# Electrotactile.net
KiCad netlist of a schematic drawn in Altium Designer
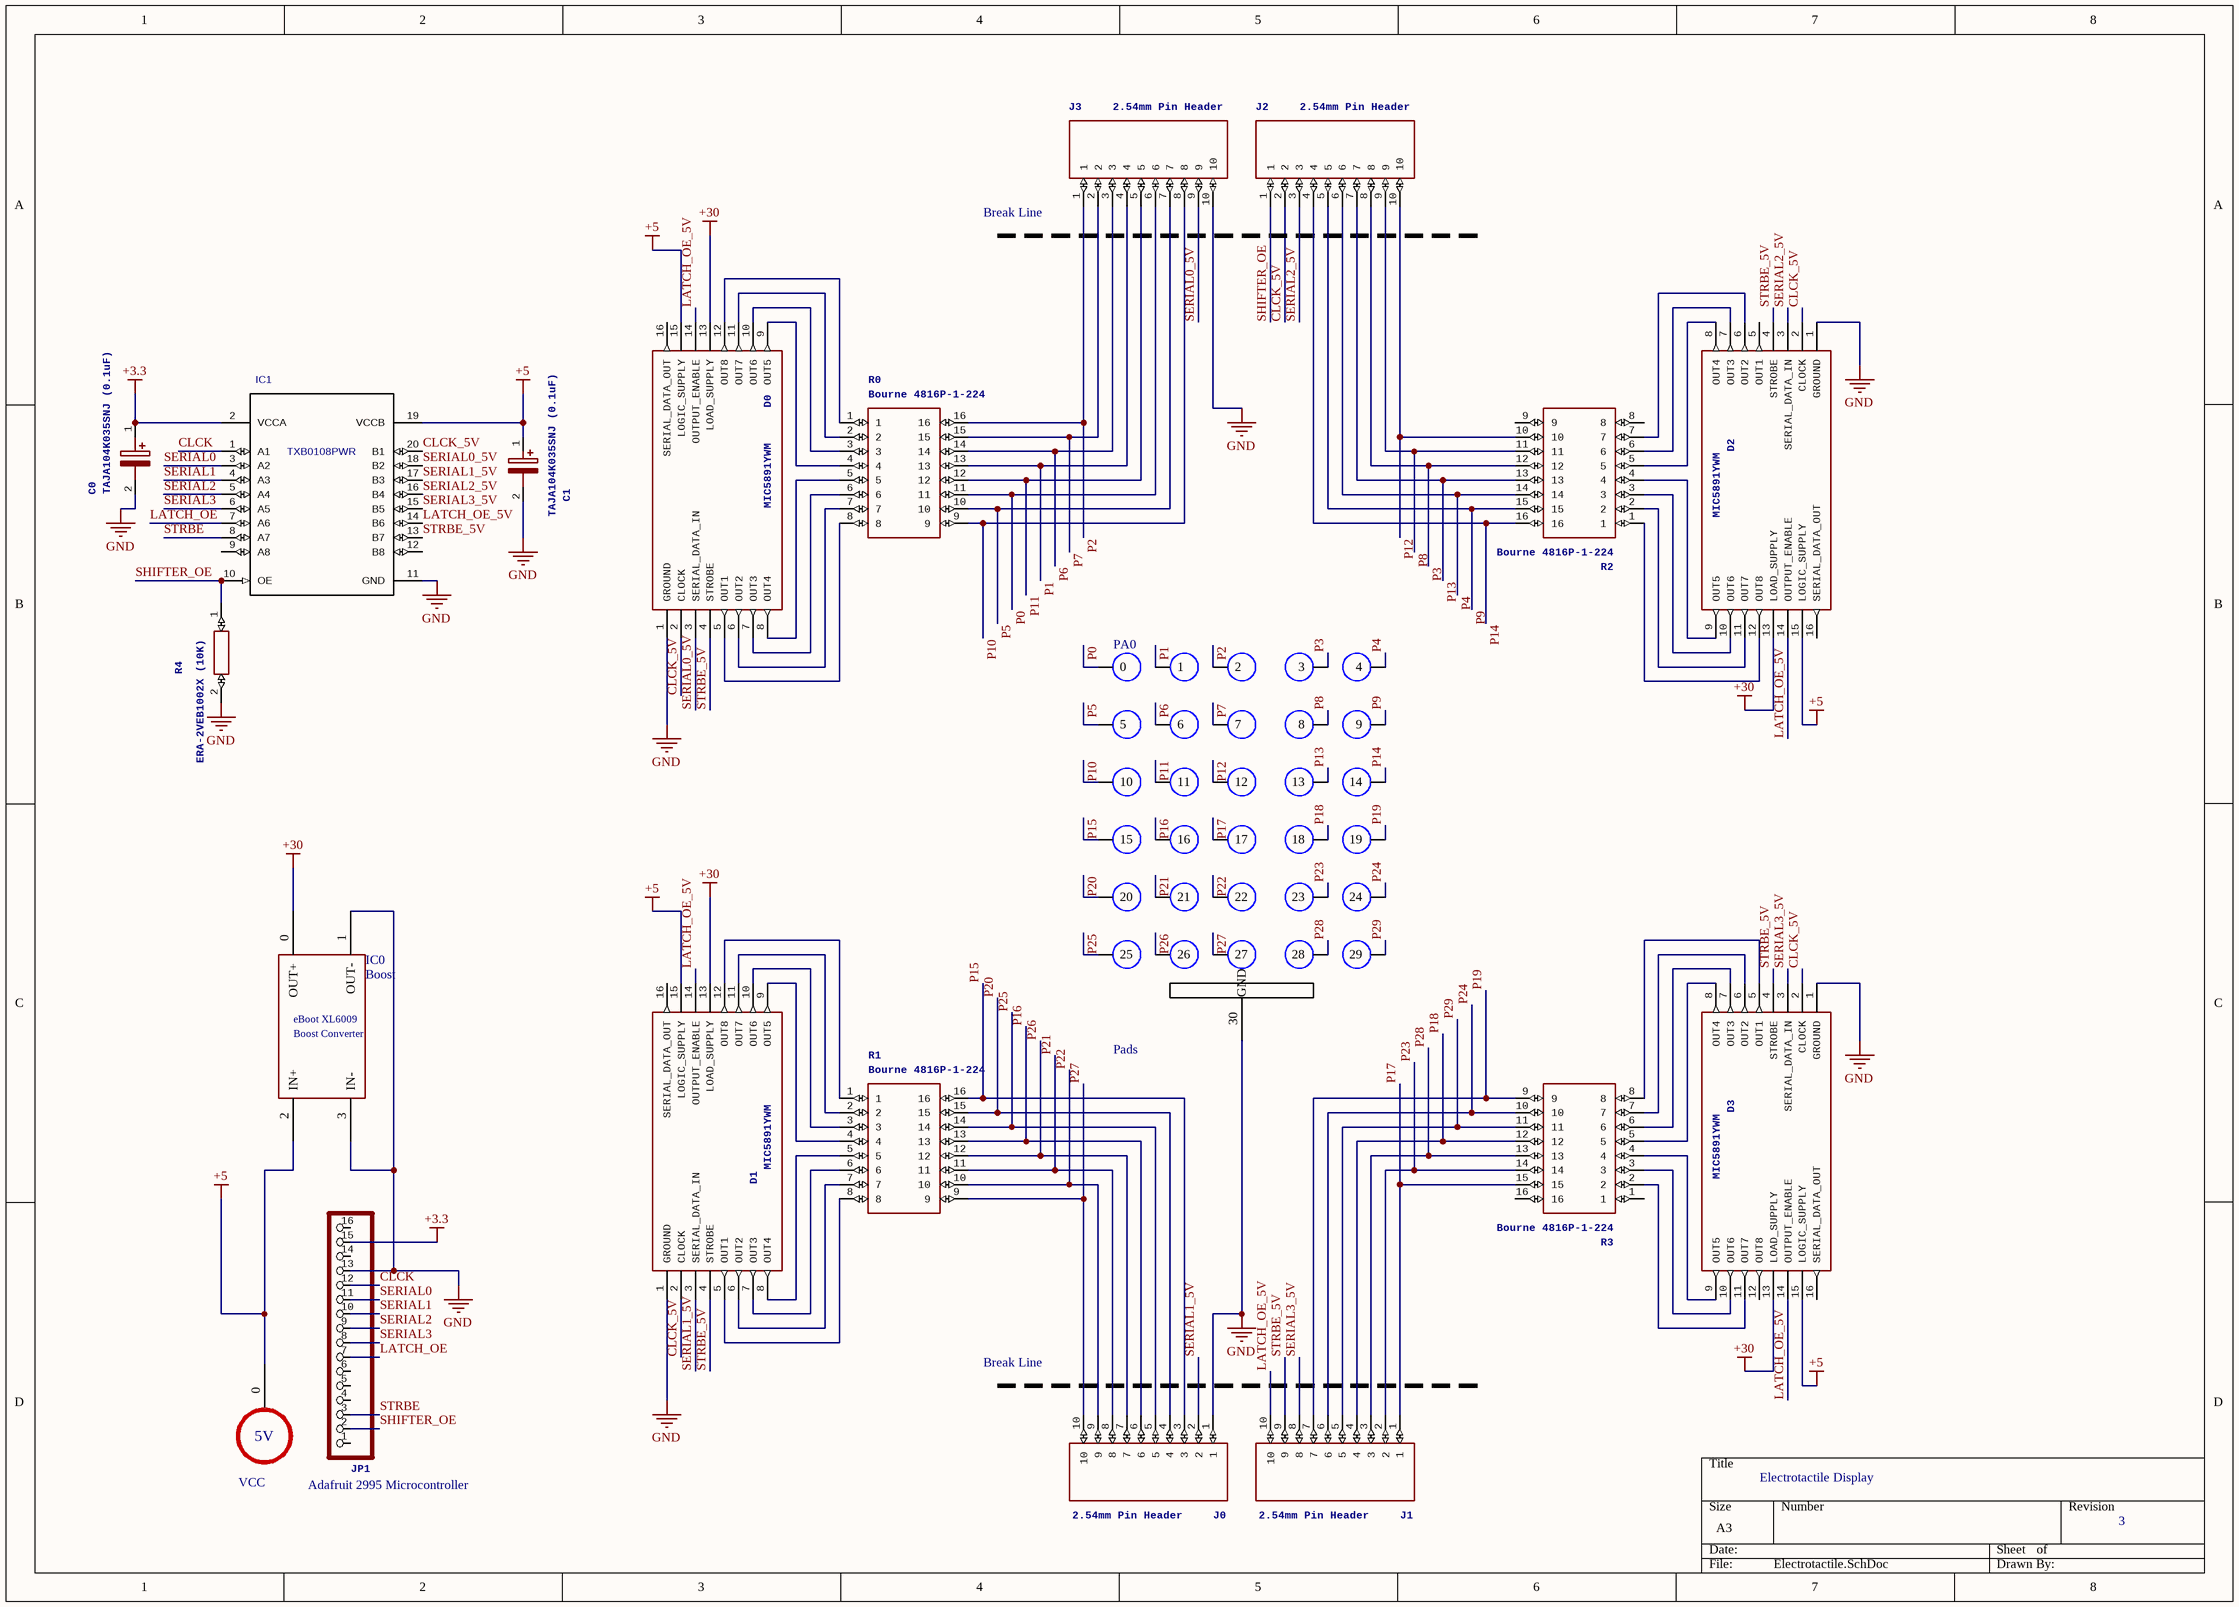
[diagram p0: Electrotactile.SchDoc]

(export (version "E")
  (design (tool "Eeschema 10.0.6"))
  (components
    (comp (ref "C0")
      (value "TAJA104K035SNJ (0.1uF)")
      (footprint "CAPPM3216X180N")
      (fields
        (field (name "MOUSER_PART_NUMBER") "581-TAJA104K035SNJ")
        (field (name "MANUFACTURER_PART_NUMBER") "TAJA104K035SNJ")
      )
      (libsource (lib "") (part "TAJA104K035SNJ_1"))
    )
    (comp (ref "C1")
      (value "TAJA104K035SNJ (0.1uF)")
      (footprint "CAPPM3216X180N")
      (fields
        (field (name "MOUSER_PART_NUMBER") "581-TAJA104K035SNJ")
        (field (name "MANUFACTURER_PART_NUMBER") "TAJA104K035SNJ")
      )
      (libsource (lib "TAJA104K035SNJ") (part "TAJA104K035SNJ"))
    )
    (comp (ref "D0")
      (value "MIC5891YWM")
      (footprint "SOIC127P1031X264-16N")
      (fields (field (name "MOUSER_PART_NUMBER") "998-MIC5891YWM"))
      (libsource (lib "MIC5891YWM") (part "MIC5891YWM"))
    )
    (comp (ref "D1")
      (value "MIC5891YWM")
      (footprint "SOIC127P1031X264-16N")
      (fields (field (name "MOUSER_PART_NUMBER") "998-MIC5891YWM"))
      (libsource (lib "MIC5891YWM") (part "MIC5891YWM"))
    )
    (comp (ref "D2")
      (value "MIC5891YWM")
      (footprint "SOIC127P1031X264-16N")
      (fields (field (name "MOUSER_PART_NUMBER") "998-MIC5891YWM"))
      (libsource (lib "MIC5891YWM") (part "MIC5891YWM"))
    )
    (comp (ref "D3")
      (value "MIC5891YWM")
      (footprint "SOIC127P1031X264-16N")
      (fields (field (name "MOUSER_PART_NUMBER") "998-MIC5891YWM"))
      (libsource (lib "MIC5891YWM") (part "MIC5891YWM"))
    )
    (comp (ref "IC0") (value "Boost") (footprint "Boost Pads") (libsource (lib "Boost") (part "Boost")))
    (comp (ref "IC1")
      (value "TXB0108PWR")
      (footprint "SOP65P640X120-20N")
      (fields (field (name "MANUFACTURER") "Texas Instruments"))
      (libsource (lib "AltiumV15") (part "TXB0108PWR"))
    )
    (comp (ref "J0")
      (value "2.54mm Pin Header")
      (footprint "HDRV10W64P0X254_1X10_2540X254X")
      (fields
        (field (name "MOUSER_PART_NUMBER") "710-61301011121")
        (field (name "MANUFACTURER_PART_NUMBER") "61301011121")
      )
      (libsource (lib "61301011121") (part "61301011121"))
    )
    (comp (ref "J1")
      (value "2.54mm Pin Header")
      (footprint "HDRV10W64P0X254_1X10_2540X254X")
      (fields
        (field (name "MOUSER_PART_NUMBER") "710-61301011121")
        (field (name "MANUFACTURER_PART_NUMBER") "61301011121")
      )
      (libsource (lib "61301011121") (part "61301011121"))
    )
    (comp (ref "J2")
      (value "2.54mm Pin Header")
      (footprint "HDRV10W64P0X254_1X10_2540X254X")
      (fields
        (field (name "MOUSER_PART_NUMBER") "710-61301011121")
        (field (name "MANUFACTURER_PART_NUMBER") "61301011121")
      )
      (libsource (lib "61301011121") (part "61301011121"))
    )
    (comp (ref "J3")
      (value "2.54mm Pin Header")
      (footprint "HDRV10W64P0X254_1X10_2540X254X")
      (fields
        (field (name "MOUSER_PART_NUMBER") "710-61301011121")
        (field (name "MANUFACTURER_PART_NUMBER") "61301011121")
      )
      (libsource (lib "61301011121") (part "61301011121"))
    )
    (comp (ref "JP1")
      (value "HEADER-1X16ROUND")
      (footprint "header_x16")
      (description "PIN HEADER")
      (libsource (lib "microbuilder") (part "HEADER-1X16ROUND"))
    )
    (comp (ref "PA0") (value "Pads") (footprint "Pads_Grid") (libsource (lib "pads") (part "Pads")))
    (comp (ref "R0")
      (value "Bourne 4816P-1-224")
      (footprint "SOIC127P762X215-16N")
      (fields
        (field (name "MOUSER_PART_NUMBER") "652-4816P-1LF-22K")
        (field (name "MANUFACTURER_PART_NUMBER") "4816P-1-223LF")
      )
      (libsource (lib "4816P-1-223LF") (part "4816P-1-223LF"))
    )
    (comp (ref "R1")
      (value "Bourne 4816P-1-224")
      (footprint "SOIC127P762X215-16N")
      (fields
        (field (name "MOUSER_PART_NUMBER") "652-4816P-1LF-22K")
        (field (name "MANUFACTURER_PART_NUMBER") "4816P-1-223LF")
      )
      (libsource (lib "4816P-1-223LF") (part "4816P-1-223LF"))
    )
    (comp (ref "R2")
      (value "Bourne 4816P-1-224")
      (footprint "SOIC127P762X215-16N")
      (fields
        (field (name "MOUSER_PART_NUMBER") "652-4816P-1LF-22K")
        (field (name "MANUFACTURER_PART_NUMBER") "4816P-1-223LF")
      )
      (libsource (lib "4816P-1-223LF") (part "4816P-1-223LF"))
    )
    (comp (ref "R3")
      (value "Bourne 4816P-1-224")
      (footprint "SOIC127P762X215-16N")
      (fields
        (field (name "MOUSER_PART_NUMBER") "652-4816P-1LF-22K")
        (field (name "MANUFACTURER_PART_NUMBER") "4816P-1-223LF")
      )
      (libsource (lib "4816P-1-223LF") (part "4816P-1-223LF"))
    )
    (comp (ref "R4")
      (value "ERA-2VEB1002X (10K)")
      (footprint "RESC1005X40N")
      (fields
        (field (name "MOUSER_PART_NUMBER") "667-ERA-2VEB1002X")
        (field (name "MANUFACTURER_PART_NUMBER") "ERA-2VEB1002X")
      )
      (libsource (lib "ERA-2VEB1002X") (part "ERA-2VEB1002X"))
    )
    (comp (ref "VCC") (value "5V") (footprint "5v_Port") (libsource (lib "5V_Port") (part "Component_1")))
  )
  (nets
    (net (code "1") (name "+3.3") (class "Default")
      (node (ref "C0") (pin "1") (pinfunction "+_1") (pintype "bidirectional"))
      (node (ref "IC1") (pin "2") (pinfunction "VCCA_2") (pintype "power_in"))
      (node (ref "JP1") (pin "15") (pinfunction "15_15") (pintype "passive"))
    )
    (net (code "2") (name "+5") (class "Default")
      (node (ref "C1") (pin "1") (pinfunction "+_1") (pintype "bidirectional"))
      (node (ref "D0") (pin "15") (pinfunction "LOGIC_SUPPLY_15") (pintype "power_in"))
      (node (ref "D1") (pin "15") (pinfunction "LOGIC_SUPPLY_15") (pintype "power_in"))
      (node (ref "D2") (pin "15") (pinfunction "LOGIC_SUPPLY_15") (pintype "power_in"))
      (node (ref "D3") (pin "15") (pinfunction "LOGIC_SUPPLY_15") (pintype "power_in"))
      (node (ref "IC0") (pin "2") (pinfunction "IN+_2") (pintype "passive"))
      (node (ref "IC1") (pin "19") (pinfunction "VCCB_19") (pintype "power_in"))
      (node (ref "VCC") (pin "0") (pinfunction "31_0") (pintype "passive"))
    )
    (net (code "3") (name "+30") (class "Default")
      (node (ref "D0") (pin "13") (pinfunction "LOAD_SUPPLY_13") (pintype "power_in"))
      (node (ref "D1") (pin "13") (pinfunction "LOAD_SUPPLY_13") (pintype "power_in"))
      (node (ref "D2") (pin "13") (pinfunction "LOAD_SUPPLY_13") (pintype "power_in"))
      (node (ref "D3") (pin "13") (pinfunction "LOAD_SUPPLY_13") (pintype "power_in"))
      (node (ref "IC0") (pin "0") (pinfunction "OUT+_0") (pintype "passive"))
    )
    (net (code "4") (name "/CLCK") (class "Default")
      (node (ref "IC1") (pin "1") (pinfunction "A1_1") (pintype "bidirectional"))
      (node (ref "JP1") (pin "12") (pinfunction "12_12") (pintype "passive"))
    )
    (net (code "5") (name "/CLCK_5V") (class "Default")
      (node (ref "D0") (pin "2") (pinfunction "CLOCK_2") (pintype "passive"))
      (node (ref "D1") (pin "2") (pinfunction "CLOCK_2") (pintype "passive"))
      (node (ref "D2") (pin "2") (pinfunction "CLOCK_2") (pintype "passive"))
      (node (ref "D3") (pin "2") (pinfunction "CLOCK_2") (pintype "passive"))
      (node (ref "IC1") (pin "20") (pinfunction "B1_20") (pintype "bidirectional"))
      (node (ref "J2") (pin "2") (pinfunction "2_2") (pintype "bidirectional"))
    )
    (net (code "6") (name "/LATCH_OE") (class "Default")
      (node (ref "IC1") (pin "7") (pinfunction "A6_7") (pintype "bidirectional"))
      (node (ref "JP1") (pin "7") (pinfunction "7_7") (pintype "passive"))
    )
    (net (code "7") (name "/LATCH_OE_5V") (class "Default")
      (node (ref "D0") (pin "14") (pinfunction "OUTPUT_ENABLE_14") (pintype "passive"))
      (node (ref "D1") (pin "14") (pinfunction "OUTPUT_ENABLE_14") (pintype "passive"))
      (node (ref "D2") (pin "14") (pinfunction "OUTPUT_ENABLE_14") (pintype "passive"))
      (node (ref "D3") (pin "14") (pinfunction "OUTPUT_ENABLE_14") (pintype "passive"))
      (node (ref "IC1") (pin "14") (pinfunction "B6_14") (pintype "bidirectional"))
      (node (ref "J1") (pin "10") (pinfunction "10_10") (pintype "bidirectional"))
    )
    (net (code "8") (name "/P0") (class "Default")
      (node (ref "J3") (pin "6") (pinfunction "6_6") (pintype "bidirectional"))
      (node (ref "PA0") (pin "0") (pinfunction "0_0") (pintype "passive"))
      (node (ref "R0") (pin "11") (pinfunction "11_11") (pintype "bidirectional"))
    )
    (net (code "9") (name "/P1") (class "Default")
      (node (ref "J3") (pin "4") (pinfunction "4_4") (pintype "bidirectional"))
      (node (ref "PA0") (pin "1") (pinfunction "1_1") (pintype "passive"))
      (node (ref "R0") (pin "13") (pinfunction "13_13") (pintype "bidirectional"))
    )
    (net (code "10") (name "/P2") (class "Default")
      (node (ref "J3") (pin "1") (pinfunction "1_1") (pintype "bidirectional"))
      (node (ref "PA0") (pin "2") (pinfunction "2_2") (pintype "passive"))
      (node (ref "R0") (pin "16") (pinfunction "16_16") (pintype "bidirectional"))
    )
    (net (code "11") (name "/P3") (class "Default")
      (node (ref "J2") (pin "8") (pinfunction "8_8") (pintype "bidirectional"))
      (node (ref "PA0") (pin "3") (pinfunction "3_3") (pintype "passive"))
      (node (ref "R2") (pin "12") (pinfunction "12_12") (pintype "bidirectional"))
    )
    (net (code "12") (name "/P4") (class "Default")
      (node (ref "J2") (pin "6") (pinfunction "6_6") (pintype "bidirectional"))
      (node (ref "PA0") (pin "4") (pinfunction "4_4") (pintype "passive"))
      (node (ref "R2") (pin "14") (pinfunction "14_14") (pintype "bidirectional"))
    )
    (net (code "13") (name "/P5") (class "Default")
      (node (ref "J3") (pin "7") (pinfunction "7_7") (pintype "bidirectional"))
      (node (ref "PA0") (pin "5") (pinfunction "5_5") (pintype "passive"))
      (node (ref "R0") (pin "10") (pinfunction "10_10") (pintype "bidirectional"))
    )
    (net (code "14") (name "/P6") (class "Default")
      (node (ref "J3") (pin "3") (pinfunction "3_3") (pintype "bidirectional"))
      (node (ref "PA0") (pin "6") (pinfunction "6_6") (pintype "passive"))
      (node (ref "R0") (pin "14") (pinfunction "14_14") (pintype "bidirectional"))
    )
    (net (code "15") (name "/P7") (class "Default")
      (node (ref "J3") (pin "2") (pinfunction "2_2") (pintype "bidirectional"))
      (node (ref "PA0") (pin "7") (pinfunction "7_7") (pintype "passive"))
      (node (ref "R0") (pin "15") (pinfunction "15_15") (pintype "bidirectional"))
    )
    (net (code "16") (name "/P8") (class "Default")
      (node (ref "J2") (pin "9") (pinfunction "9_9") (pintype "bidirectional"))
      (node (ref "PA0") (pin "8") (pinfunction "8_8") (pintype "passive"))
      (node (ref "R2") (pin "11") (pinfunction "11_11") (pintype "bidirectional"))
    )
    (net (code "17") (name "/P9") (class "Default")
      (node (ref "J2") (pin "5") (pinfunction "5_5") (pintype "bidirectional"))
      (node (ref "PA0") (pin "9") (pinfunction "9_9") (pintype "passive"))
      (node (ref "R2") (pin "15") (pinfunction "15_15") (pintype "bidirectional"))
    )
    (net (code "18") (name "/P10") (class "Default")
      (node (ref "J3") (pin "8") (pinfunction "8_8") (pintype "bidirectional"))
      (node (ref "PA0") (pin "10") (pinfunction "10_10") (pintype "passive"))
      (node (ref "R0") (pin "9") (pinfunction "9_9") (pintype "bidirectional"))
    )
    (net (code "19") (name "/P11") (class "Default")
      (node (ref "J3") (pin "5") (pinfunction "5_5") (pintype "bidirectional"))
      (node (ref "PA0") (pin "11") (pinfunction "11_11") (pintype "passive"))
      (node (ref "R0") (pin "12") (pinfunction "12_12") (pintype "bidirectional"))
    )
    (net (code "20") (name "/P12") (class "Default")
      (node (ref "J2") (pin "10") (pinfunction "10_10") (pintype "bidirectional"))
      (node (ref "PA0") (pin "12") (pinfunction "12_12") (pintype "passive"))
      (node (ref "R2") (pin "10") (pinfunction "10_10") (pintype "bidirectional"))
    )
    (net (code "21") (name "/P13") (class "Default")
      (node (ref "J2") (pin "7") (pinfunction "7_7") (pintype "bidirectional"))
      (node (ref "PA0") (pin "13") (pinfunction "13_13") (pintype "passive"))
      (node (ref "R2") (pin "13") (pinfunction "13_13") (pintype "bidirectional"))
    )
    (net (code "22") (name "/P14") (class "Default")
      (node (ref "J2") (pin "4") (pinfunction "4_4") (pintype "bidirectional"))
      (node (ref "PA0") (pin "14") (pinfunction "14_14") (pintype "passive"))
      (node (ref "R2") (pin "16") (pinfunction "16_16") (pintype "bidirectional"))
    )
    (net (code "23") (name "/P15") (class "Default")
      (node (ref "J0") (pin "3") (pinfunction "3_3") (pintype "bidirectional"))
      (node (ref "PA0") (pin "15") (pinfunction "15_15") (pintype "passive"))
      (node (ref "R1") (pin "16") (pinfunction "16_16") (pintype "bidirectional"))
    )
    (net (code "24") (name "/P16") (class "Default")
      (node (ref "J0") (pin "6") (pinfunction "6_6") (pintype "bidirectional"))
      (node (ref "PA0") (pin "16") (pinfunction "16_16") (pintype "passive"))
      (node (ref "R1") (pin "13") (pinfunction "13_13") (pintype "bidirectional"))
    )
    (net (code "25") (name "/P17") (class "Default")
      (node (ref "J1") (pin "1") (pinfunction "1_1") (pintype "bidirectional"))
      (node (ref "PA0") (pin "17") (pinfunction "17_17") (pintype "passive"))
      (node (ref "R3") (pin "15") (pinfunction "15_15") (pintype "bidirectional"))
    )
    (net (code "26") (name "/P18") (class "Default")
      (node (ref "J1") (pin "4") (pinfunction "4_4") (pintype "bidirectional"))
      (node (ref "PA0") (pin "18") (pinfunction "18_18") (pintype "passive"))
      (node (ref "R3") (pin "12") (pinfunction "12_12") (pintype "bidirectional"))
    )
    (net (code "27") (name "/P19") (class "Default")
      (node (ref "J1") (pin "7") (pinfunction "7_7") (pintype "bidirectional"))
      (node (ref "PA0") (pin "19") (pinfunction "19_19") (pintype "passive"))
      (node (ref "R3") (pin "9") (pinfunction "9_9") (pintype "bidirectional"))
    )
    (net (code "28") (name "/P20") (class "Default")
      (node (ref "J0") (pin "4") (pinfunction "4_4") (pintype "bidirectional"))
      (node (ref "PA0") (pin "20") (pinfunction "20_20") (pintype "passive"))
      (node (ref "R1") (pin "15") (pinfunction "15_15") (pintype "bidirectional"))
    )
    (net (code "29") (name "/P21") (class "Default")
      (node (ref "J0") (pin "8") (pinfunction "8_8") (pintype "bidirectional"))
      (node (ref "PA0") (pin "21") (pinfunction "21_21") (pintype "passive"))
      (node (ref "R1") (pin "11") (pinfunction "11_11") (pintype "bidirectional"))
    )
    (net (code "30") (name "/P22") (class "Default")
      (node (ref "J0") (pin "9") (pinfunction "9_9") (pintype "bidirectional"))
      (node (ref "PA0") (pin "22") (pinfunction "22_22") (pintype "passive"))
      (node (ref "R1") (pin "10") (pinfunction "10_10") (pintype "bidirectional"))
    )
    (net (code "31") (name "/P23") (class "Default")
      (node (ref "J1") (pin "2") (pinfunction "2_2") (pintype "bidirectional"))
      (node (ref "PA0") (pin "23") (pinfunction "23_23") (pintype "passive"))
      (node (ref "R3") (pin "14") (pinfunction "14_14") (pintype "bidirectional"))
    )
    (net (code "32") (name "/P24") (class "Default")
      (node (ref "J1") (pin "6") (pinfunction "6_6") (pintype "bidirectional"))
      (node (ref "PA0") (pin "24") (pinfunction "24_24") (pintype "passive"))
      (node (ref "R3") (pin "10") (pinfunction "10_10") (pintype "bidirectional"))
    )
    (net (code "33") (name "/P25") (class "Default")
      (node (ref "J0") (pin "5") (pinfunction "5_5") (pintype "bidirectional"))
      (node (ref "PA0") (pin "25") (pinfunction "25_25") (pintype "passive"))
      (node (ref "R1") (pin "14") (pinfunction "14_14") (pintype "bidirectional"))
    )
    (net (code "34") (name "/P26") (class "Default")
      (node (ref "J0") (pin "7") (pinfunction "7_7") (pintype "bidirectional"))
      (node (ref "PA0") (pin "26") (pinfunction "26_26") (pintype "passive"))
      (node (ref "R1") (pin "12") (pinfunction "12_12") (pintype "bidirectional"))
    )
    (net (code "35") (name "/P27") (class "Default")
      (node (ref "J0") (pin "10") (pinfunction "10_10") (pintype "bidirectional"))
      (node (ref "PA0") (pin "27") (pinfunction "27_27") (pintype "passive"))
      (node (ref "R1") (pin "9") (pinfunction "9_9") (pintype "bidirectional"))
    )
    (net (code "36") (name "/P28") (class "Default")
      (node (ref "J1") (pin "3") (pinfunction "3_3") (pintype "bidirectional"))
      (node (ref "PA0") (pin "28") (pinfunction "28_28") (pintype "passive"))
      (node (ref "R3") (pin "13") (pinfunction "13_13") (pintype "bidirectional"))
    )
    (net (code "37") (name "/P29") (class "Default")
      (node (ref "J1") (pin "5") (pinfunction "5_5") (pintype "bidirectional"))
      (node (ref "PA0") (pin "29") (pinfunction "29_29") (pintype "passive"))
      (node (ref "R3") (pin "11") (pinfunction "11_11") (pintype "bidirectional"))
    )
    (net (code "38") (name "/SERIAL0") (class "Default")
      (node (ref "IC1") (pin "3") (pinfunction "A2_3") (pintype "bidirectional"))
      (node (ref "JP1") (pin "11") (pinfunction "11_11") (pintype "passive"))
    )
    (net (code "39") (name "/SERIAL0_5V") (class "Default")
      (node (ref "D0") (pin "3") (pinfunction "SERIAL_DATA_IN_3") (pintype "passive"))
      (node (ref "IC1") (pin "18") (pinfunction "B2_18") (pintype "bidirectional"))
      (node (ref "J3") (pin "9") (pinfunction "9_9") (pintype "bidirectional"))
    )
    (net (code "40") (name "/SERIAL1") (class "Default")
      (node (ref "IC1") (pin "4") (pinfunction "A3_4") (pintype "bidirectional"))
      (node (ref "JP1") (pin "10") (pinfunction "10_10") (pintype "passive"))
    )
    (net (code "41") (name "/SERIAL1_5V") (class "Default")
      (node (ref "D1") (pin "3") (pinfunction "SERIAL_DATA_IN_3") (pintype "passive"))
      (node (ref "IC1") (pin "17") (pinfunction "B3_17") (pintype "bidirectional"))
      (node (ref "J0") (pin "2") (pinfunction "2_2") (pintype "bidirectional"))
    )
    (net (code "42") (name "/SERIAL2") (class "Default")
      (node (ref "IC1") (pin "5") (pinfunction "A4_5") (pintype "bidirectional"))
      (node (ref "JP1") (pin "9") (pinfunction "9_9") (pintype "passive"))
    )
    (net (code "43") (name "/SERIAL2_5V") (class "Default")
      (node (ref "D2") (pin "3") (pinfunction "SERIAL_DATA_IN_3") (pintype "passive"))
      (node (ref "IC1") (pin "16") (pinfunction "B4_16") (pintype "bidirectional"))
      (node (ref "J2") (pin "3") (pinfunction "3_3") (pintype "bidirectional"))
    )
    (net (code "44") (name "/SERIAL3") (class "Default")
      (node (ref "IC1") (pin "6") (pinfunction "A5_6") (pintype "bidirectional"))
      (node (ref "JP1") (pin "8") (pinfunction "8_8") (pintype "passive"))
    )
    (net (code "45") (name "/SERIAL3_5V") (class "Default")
      (node (ref "D3") (pin "3") (pinfunction "SERIAL_DATA_IN_3") (pintype "passive"))
      (node (ref "IC1") (pin "15") (pinfunction "B5_15") (pintype "bidirectional"))
      (node (ref "J1") (pin "8") (pinfunction "8_8") (pintype "bidirectional"))
    )
    (net (code "46") (name "/SHIFTER_OE") (class "Default")
      (node (ref "IC1") (pin "10") (pinfunction "OE_10") (pintype "input"))
      (node (ref "J2") (pin "1") (pinfunction "1_1") (pintype "bidirectional"))
      (node (ref "JP1") (pin "2") (pinfunction "2_2") (pintype "passive"))
      (node (ref "R4") (pin "1") (pinfunction "1_1") (pintype "bidirectional"))
    )
    (net (code "47") (name "/STRBE") (class "Default")
      (node (ref "IC1") (pin "8") (pinfunction "A7_8") (pintype "bidirectional"))
      (node (ref "JP1") (pin "3") (pinfunction "3_3") (pintype "passive"))
    )
    (net (code "48") (name "/STRBE_5V") (class "Default")
      (node (ref "D0") (pin "4") (pinfunction "STROBE_4") (pintype "passive"))
      (node (ref "D1") (pin "4") (pinfunction "STROBE_4") (pintype "passive"))
      (node (ref "D2") (pin "4") (pinfunction "STROBE_4") (pintype "passive"))
      (node (ref "D3") (pin "4") (pinfunction "STROBE_4") (pintype "passive"))
      (node (ref "IC1") (pin "13") (pinfunction "B7_13") (pintype "bidirectional"))
      (node (ref "J1") (pin "9") (pinfunction "9_9") (pintype "bidirectional"))
    )
    (net (code "49") (name "GND") (class "Default")
      (node (ref "C0") (pin "2") (pinfunction "-_2") (pintype "bidirectional"))
      (node (ref "C1") (pin "2") (pinfunction "-_2") (pintype "bidirectional"))
      (node (ref "D0") (pin "1") (pinfunction "GROUND_1") (pintype "power_in"))
      (node (ref "D1") (pin "1") (pinfunction "GROUND_1") (pintype "power_in"))
      (node (ref "D2") (pin "1") (pinfunction "GROUND_1") (pintype "power_in"))
      (node (ref "D3") (pin "1") (pinfunction "GROUND_1") (pintype "power_in"))
      (node (ref "IC0") (pin "1") (pinfunction "OUT-_1") (pintype "passive"))
      (node (ref "IC0") (pin "3") (pinfunction "IN-_3") (pintype "passive"))
      (node (ref "IC1") (pin "11") (pinfunction "GND_11") (pintype "power_in"))
      (node (ref "J0") (pin "1") (pinfunction "1_1") (pintype "bidirectional"))
      (node (ref "J3") (pin "10") (pinfunction "10_10") (pintype "bidirectional"))
      (node (ref "JP1") (pin "13") (pinfunction "13_13") (pintype "passive"))
      (node (ref "PA0") (pin "30") (pinfunction "GND_30") (pintype "passive"))
      (node (ref "R4") (pin "2") (pinfunction "2_2") (pintype "bidirectional"))
    )
    (net (code "50") (name "Net-(D0-OUT1)") (class "Default")
      (node (ref "D0") (pin "5") (pinfunction "OUT1_5") (pintype "output"))
      (node (ref "R0") (pin "8") (pinfunction "8_8") (pintype "bidirectional"))
    )
    (net (code "51") (name "Net-(D0-OUT2)") (class "Default")
      (node (ref "D0") (pin "6") (pinfunction "OUT2_6") (pintype "output"))
      (node (ref "R0") (pin "7") (pinfunction "7_7") (pintype "bidirectional"))
    )
    (net (code "52") (name "Net-(D0-OUT3)") (class "Default")
      (node (ref "D0") (pin "7") (pinfunction "OUT3_7") (pintype "output"))
      (node (ref "R0") (pin "6") (pinfunction "6_6") (pintype "bidirectional"))
    )
    (net (code "53") (name "Net-(D0-OUT4)") (class "Default")
      (node (ref "D0") (pin "8") (pinfunction "OUT4_8") (pintype "output"))
      (node (ref "R0") (pin "5") (pinfunction "5_5") (pintype "bidirectional"))
    )
    (net (code "54") (name "Net-(D0-OUT5)") (class "Default")
      (node (ref "D0") (pin "9") (pinfunction "OUT5_9") (pintype "output"))
      (node (ref "R0") (pin "4") (pinfunction "4_4") (pintype "bidirectional"))
    )
    (net (code "55") (name "Net-(D0-OUT6)") (class "Default")
      (node (ref "D0") (pin "10") (pinfunction "OUT6_10") (pintype "output"))
      (node (ref "R0") (pin "3") (pinfunction "3_3") (pintype "bidirectional"))
    )
    (net (code "56") (name "Net-(D0-OUT7)") (class "Default")
      (node (ref "D0") (pin "11") (pinfunction "OUT7_11") (pintype "output"))
      (node (ref "R0") (pin "2") (pinfunction "2_2") (pintype "bidirectional"))
    )
    (net (code "57") (name "Net-(D0-OUT8)") (class "Default")
      (node (ref "D0") (pin "12") (pinfunction "OUT8_12") (pintype "output"))
      (node (ref "R0") (pin "1") (pinfunction "1_1") (pintype "bidirectional"))
    )
    (net (code "58") (name "Net-(D1-OUT1)") (class "Default")
      (node (ref "D1") (pin "5") (pinfunction "OUT1_5") (pintype "output"))
      (node (ref "R1") (pin "8") (pinfunction "8_8") (pintype "bidirectional"))
    )
    (net (code "59") (name "Net-(D1-OUT2)") (class "Default")
      (node (ref "D1") (pin "6") (pinfunction "OUT2_6") (pintype "output"))
      (node (ref "R1") (pin "7") (pinfunction "7_7") (pintype "bidirectional"))
    )
    (net (code "60") (name "Net-(D1-OUT3)") (class "Default")
      (node (ref "D1") (pin "7") (pinfunction "OUT3_7") (pintype "output"))
      (node (ref "R1") (pin "6") (pinfunction "6_6") (pintype "bidirectional"))
    )
    (net (code "61") (name "Net-(D1-OUT4)") (class "Default")
      (node (ref "D1") (pin "8") (pinfunction "OUT4_8") (pintype "output"))
      (node (ref "R1") (pin "5") (pinfunction "5_5") (pintype "bidirectional"))
    )
    (net (code "62") (name "Net-(D1-OUT5)") (class "Default")
      (node (ref "D1") (pin "9") (pinfunction "OUT5_9") (pintype "output"))
      (node (ref "R1") (pin "4") (pinfunction "4_4") (pintype "bidirectional"))
    )
    (net (code "63") (name "Net-(D1-OUT6)") (class "Default")
      (node (ref "D1") (pin "10") (pinfunction "OUT6_10") (pintype "output"))
      (node (ref "R1") (pin "3") (pinfunction "3_3") (pintype "bidirectional"))
    )
    (net (code "64") (name "Net-(D1-OUT7)") (class "Default")
      (node (ref "D1") (pin "11") (pinfunction "OUT7_11") (pintype "output"))
      (node (ref "R1") (pin "2") (pinfunction "2_2") (pintype "bidirectional"))
    )
    (net (code "65") (name "Net-(D1-OUT8)") (class "Default")
      (node (ref "D1") (pin "12") (pinfunction "OUT8_12") (pintype "output"))
      (node (ref "R1") (pin "1") (pinfunction "1_1") (pintype "bidirectional"))
    )
    (net (code "66") (name "Net-(D2-OUT2)") (class "Default")
      (node (ref "D2") (pin "6") (pinfunction "OUT2_6") (pintype "output"))
      (node (ref "R2") (pin "7") (pinfunction "7_7") (pintype "bidirectional"))
    )
    (net (code "67") (name "Net-(D2-OUT3)") (class "Default")
      (node (ref "D2") (pin "7") (pinfunction "OUT3_7") (pintype "output"))
      (node (ref "R2") (pin "6") (pinfunction "6_6") (pintype "bidirectional"))
    )
    (net (code "68") (name "Net-(D2-OUT4)") (class "Default")
      (node (ref "D2") (pin "8") (pinfunction "OUT4_8") (pintype "output"))
      (node (ref "R2") (pin "5") (pinfunction "5_5") (pintype "bidirectional"))
    )
    (net (code "69") (name "Net-(D2-OUT5)") (class "Default")
      (node (ref "D2") (pin "9") (pinfunction "OUT5_9") (pintype "output"))
      (node (ref "R2") (pin "4") (pinfunction "4_4") (pintype "bidirectional"))
    )
    (net (code "70") (name "Net-(D2-OUT6)") (class "Default")
      (node (ref "D2") (pin "10") (pinfunction "OUT6_10") (pintype "output"))
      (node (ref "R2") (pin "3") (pinfunction "3_3") (pintype "bidirectional"))
    )
    (net (code "71") (name "Net-(D2-OUT7)") (class "Default")
      (node (ref "D2") (pin "11") (pinfunction "OUT7_11") (pintype "output"))
      (node (ref "R2") (pin "2") (pinfunction "2_2") (pintype "bidirectional"))
    )
    (net (code "72") (name "Net-(D2-OUT8)") (class "Default")
      (node (ref "D2") (pin "12") (pinfunction "OUT8_12") (pintype "output"))
      (node (ref "R2") (pin "1") (pinfunction "1_1") (pintype "bidirectional"))
    )
    (net (code "73") (name "Net-(D3-OUT1)") (class "Default")
      (node (ref "D3") (pin "5") (pinfunction "OUT1_5") (pintype "output"))
      (node (ref "R3") (pin "8") (pinfunction "8_8") (pintype "bidirectional"))
    )
    (net (code "74") (name "Net-(D3-OUT2)") (class "Default")
      (node (ref "D3") (pin "6") (pinfunction "OUT2_6") (pintype "output"))
      (node (ref "R3") (pin "7") (pinfunction "7_7") (pintype "bidirectional"))
    )
    (net (code "75") (name "Net-(D3-OUT3)") (class "Default")
      (node (ref "D3") (pin "7") (pinfunction "OUT3_7") (pintype "output"))
      (node (ref "R3") (pin "6") (pinfunction "6_6") (pintype "bidirectional"))
    )
    (net (code "76") (name "Net-(D3-OUT4)") (class "Default")
      (node (ref "D3") (pin "8") (pinfunction "OUT4_8") (pintype "output"))
      (node (ref "R3") (pin "5") (pinfunction "5_5") (pintype "bidirectional"))
    )
    (net (code "77") (name "Net-(D3-OUT5)") (class "Default")
      (node (ref "D3") (pin "9") (pinfunction "OUT5_9") (pintype "output"))
      (node (ref "R3") (pin "4") (pinfunction "4_4") (pintype "bidirectional"))
    )
    (net (code "78") (name "Net-(D3-OUT6)") (class "Default")
      (node (ref "D3") (pin "10") (pinfunction "OUT6_10") (pintype "output"))
      (node (ref "R3") (pin "3") (pinfunction "3_3") (pintype "bidirectional"))
    )
    (net (code "79") (name "Net-(D3-OUT7)") (class "Default")
      (node (ref "D3") (pin "11") (pinfunction "OUT7_11") (pintype "output"))
      (node (ref "R3") (pin "2") (pinfunction "2_2") (pintype "bidirectional"))
    )
    (net (code "80") (name "unconnected-(D0-SERIAL_DATA_OUT-Pad16)") (class "Default")
      (node (ref "D0") (pin "16") (pinfunction "SERIAL_DATA_OUT_16") (pintype "output"))
    )
    (net (code "81") (name "unconnected-(D1-SERIAL_DATA_OUT-Pad16)") (class "Default")
      (node (ref "D1") (pin "16") (pinfunction "SERIAL_DATA_OUT_16") (pintype "output"))
    )
    (net (code "82") (name "unconnected-(D2-OUT1-Pad5)") (class "Default")
      (node (ref "D2") (pin "5") (pinfunction "OUT1_5") (pintype "output"))
    )
    (net (code "83") (name "unconnected-(D2-SERIAL_DATA_OUT-Pad16)") (class "Default")
      (node (ref "D2") (pin "16") (pinfunction "SERIAL_DATA_OUT_16") (pintype "output"))
    )
    (net (code "84") (name "unconnected-(D3-OUT8-Pad12)") (class "Default")
      (node (ref "D3") (pin "12") (pinfunction "OUT8_12") (pintype "output"))
    )
    (net (code "85") (name "unconnected-(D3-SERIAL_DATA_OUT-Pad16)") (class "Default")
      (node (ref "D3") (pin "16") (pinfunction "SERIAL_DATA_OUT_16") (pintype "output"))
    )
    (net (code "86") (name "unconnected-(IC1-A8-Pad9)") (class "Default")
      (node (ref "IC1") (pin "9") (pinfunction "A8_9") (pintype "bidirectional"))
    )
    (net (code "87") (name "unconnected-(IC1-B8-Pad12)") (class "Default")
      (node (ref "IC1") (pin "12") (pinfunction "B8_12") (pintype "bidirectional"))
    )
    (net (code "88") (name "unconnected-(JP1-Pad1)") (class "Default")
      (node (ref "JP1") (pin "1") (pinfunction "1_1") (pintype "passive"))
    )
    (net (code "89") (name "unconnected-(JP1-Pad4)") (class "Default")
      (node (ref "JP1") (pin "4") (pinfunction "4_4") (pintype "passive"))
    )
    (net (code "90") (name "unconnected-(JP1-Pad5)") (class "Default")
      (node (ref "JP1") (pin "5") (pinfunction "5_5") (pintype "passive"))
    )
    (net (code "91") (name "unconnected-(JP1-Pad6)") (class "Default")
      (node (ref "JP1") (pin "6") (pinfunction "6_6") (pintype "passive"))
    )
    (net (code "92") (name "unconnected-(JP1-Pad14)") (class "Default")
      (node (ref "JP1") (pin "14") (pinfunction "14_14") (pintype "passive"))
    )
    (net (code "93") (name "unconnected-(JP1-Pad16)") (class "Default")
      (node (ref "JP1") (pin "16") (pinfunction "16_16") (pintype "passive"))
    )
    (net (code "94") (name "unconnected-(R2-Pad8)") (class "Default")
      (node (ref "R2") (pin "8") (pinfunction "8_8") (pintype "bidirectional"))
    )
    (net (code "95") (name "unconnected-(R2-Pad9)") (class "Default")
      (node (ref "R2") (pin "9") (pinfunction "9_9") (pintype "bidirectional"))
    )
    (net (code "96") (name "unconnected-(R3-Pad1)") (class "Default")
      (node (ref "R3") (pin "1") (pinfunction "1_1") (pintype "bidirectional"))
    )
    (net (code "97") (name "unconnected-(R3-Pad16)") (class "Default")
      (node (ref "R3") (pin "16") (pinfunction "16_16") (pintype "bidirectional"))
    )
  )
)
